# main.net
KiCad netlist of a schematic drawn in EAGLE
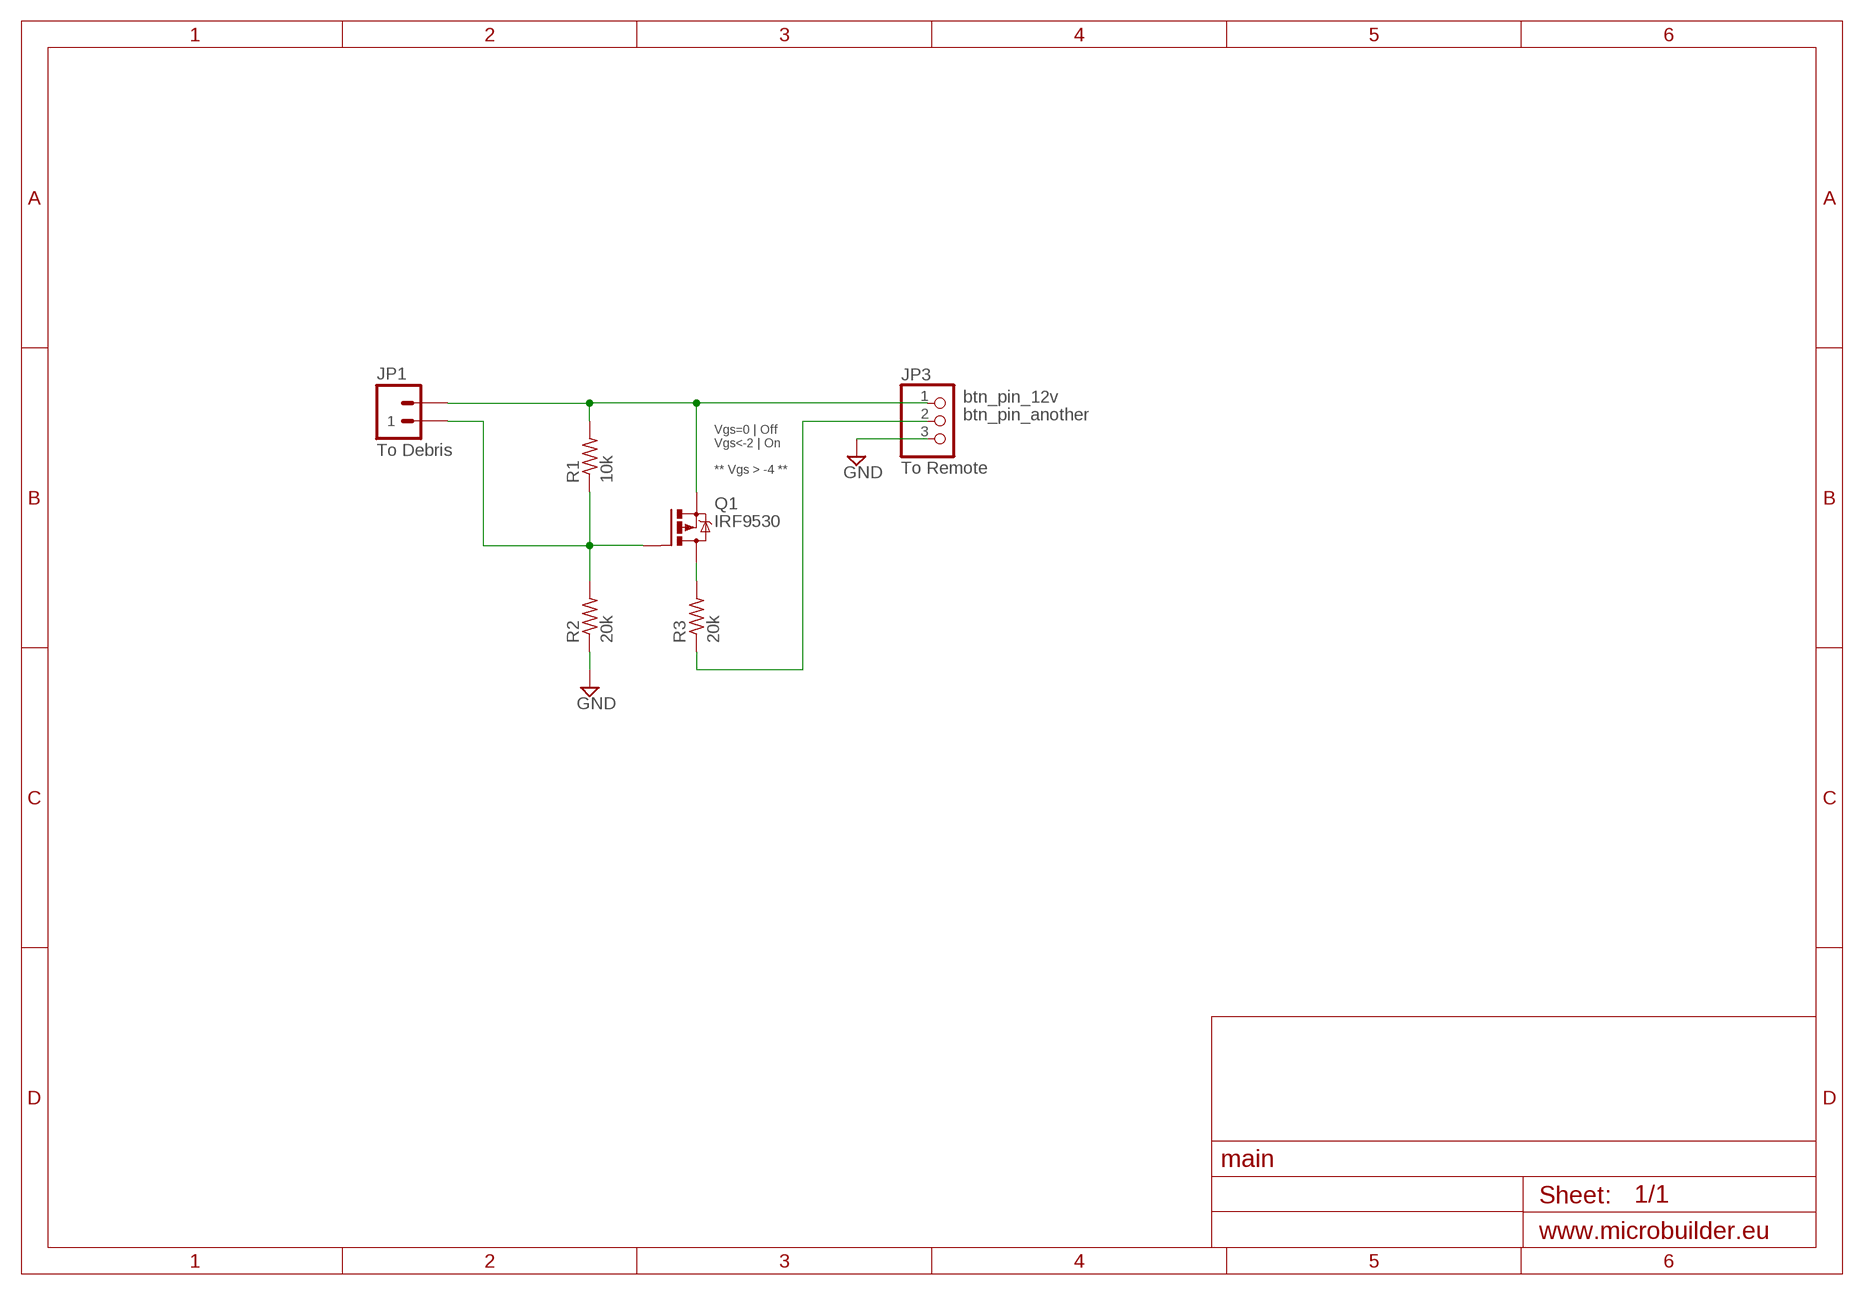
[diagram p0: schematic, sheet 1]

(export (version "E")
  (design (tool "Eeschema 10.0.6"))
  (components
    (comp (ref "JP1")
      (value "To Debris")
      (footprint "eagle-import:1X02")
      (libsource (lib "eagle-import") (part "M02PTH"))
    )
    (comp (ref "JP3")
      (value "To Remote")
      (footprint "eagle-import:1X03_OVAL")
      (libsource (lib "eagle-import") (part "HEADER-1X3"))
    )
    (comp (ref "Q1")
      (value "IRF9530")
      (footprint "eagle-import:TO220BV")
      (libsource (lib "eagle-import") (part "IRF9530"))
    )
    (comp (ref "R1")
      (value "10k")
      (footprint "eagle-import:RCL_0204_5")
      (libsource (lib "eagle-import") (part "RCL_R-US0204/5"))
    )
    (comp (ref "R2")
      (value "20k")
      (footprint "eagle-import:RCL_0204_5")
      (libsource (lib "eagle-import") (part "RCL_R-US0204/5"))
    )
    (comp (ref "R3")
      (value "20k")
      (footprint "eagle-import:RCL_0204_5")
      (libsource (lib "eagle-import") (part "RCL_R-US0204/5"))
    )
  )
  (nets
    (net (code "1") (name "GND") (class "Default")
      (node (ref "JP3") (pin "3") (pinfunction "3_3") (pintype "passive"))
      (node (ref "R2") (pin "1") (pinfunction "1_1") (pintype "passive"))
    )
    (net (code "2") (name "Net-(JP1-Pad1)") (class "Default")
      (node (ref "JP1") (pin "1") (pinfunction "1_1") (pintype "passive"))
      (node (ref "Q1") (pin "G") (pinfunction "G_G") (pintype "passive"))
      (node (ref "R1") (pin "1") (pinfunction "1_1") (pintype "passive"))
      (node (ref "R2") (pin "2") (pinfunction "2_2") (pintype "passive"))
    )
    (net (code "3") (name "Net-(JP1-Pad2)") (class "Default")
      (node (ref "JP1") (pin "2") (pinfunction "2_2") (pintype "passive"))
      (node (ref "JP3") (pin "1") (pinfunction "1_1") (pintype "passive"))
      (node (ref "Q1") (pin "S") (pinfunction "S_S") (pintype "passive"))
      (node (ref "R1") (pin "2") (pinfunction "2_2") (pintype "passive"))
    )
    (net (code "4") (name "Net-(JP3-Pad2)") (class "Default")
      (node (ref "JP3") (pin "2") (pinfunction "2_2") (pintype "passive"))
      (node (ref "R3") (pin "1") (pinfunction "1_1") (pintype "passive"))
    )
    (net (code "5") (name "Net-(Q1-PadD)") (class "Default")
      (node (ref "Q1") (pin "D") (pinfunction "D_D") (pintype "passive"))
      (node (ref "R3") (pin "2") (pinfunction "2_2") (pintype "passive"))
    )
  )
)
